# LS7366R_TestPRoject.net
KiCad netlist of a schematic drawn in EAGLE
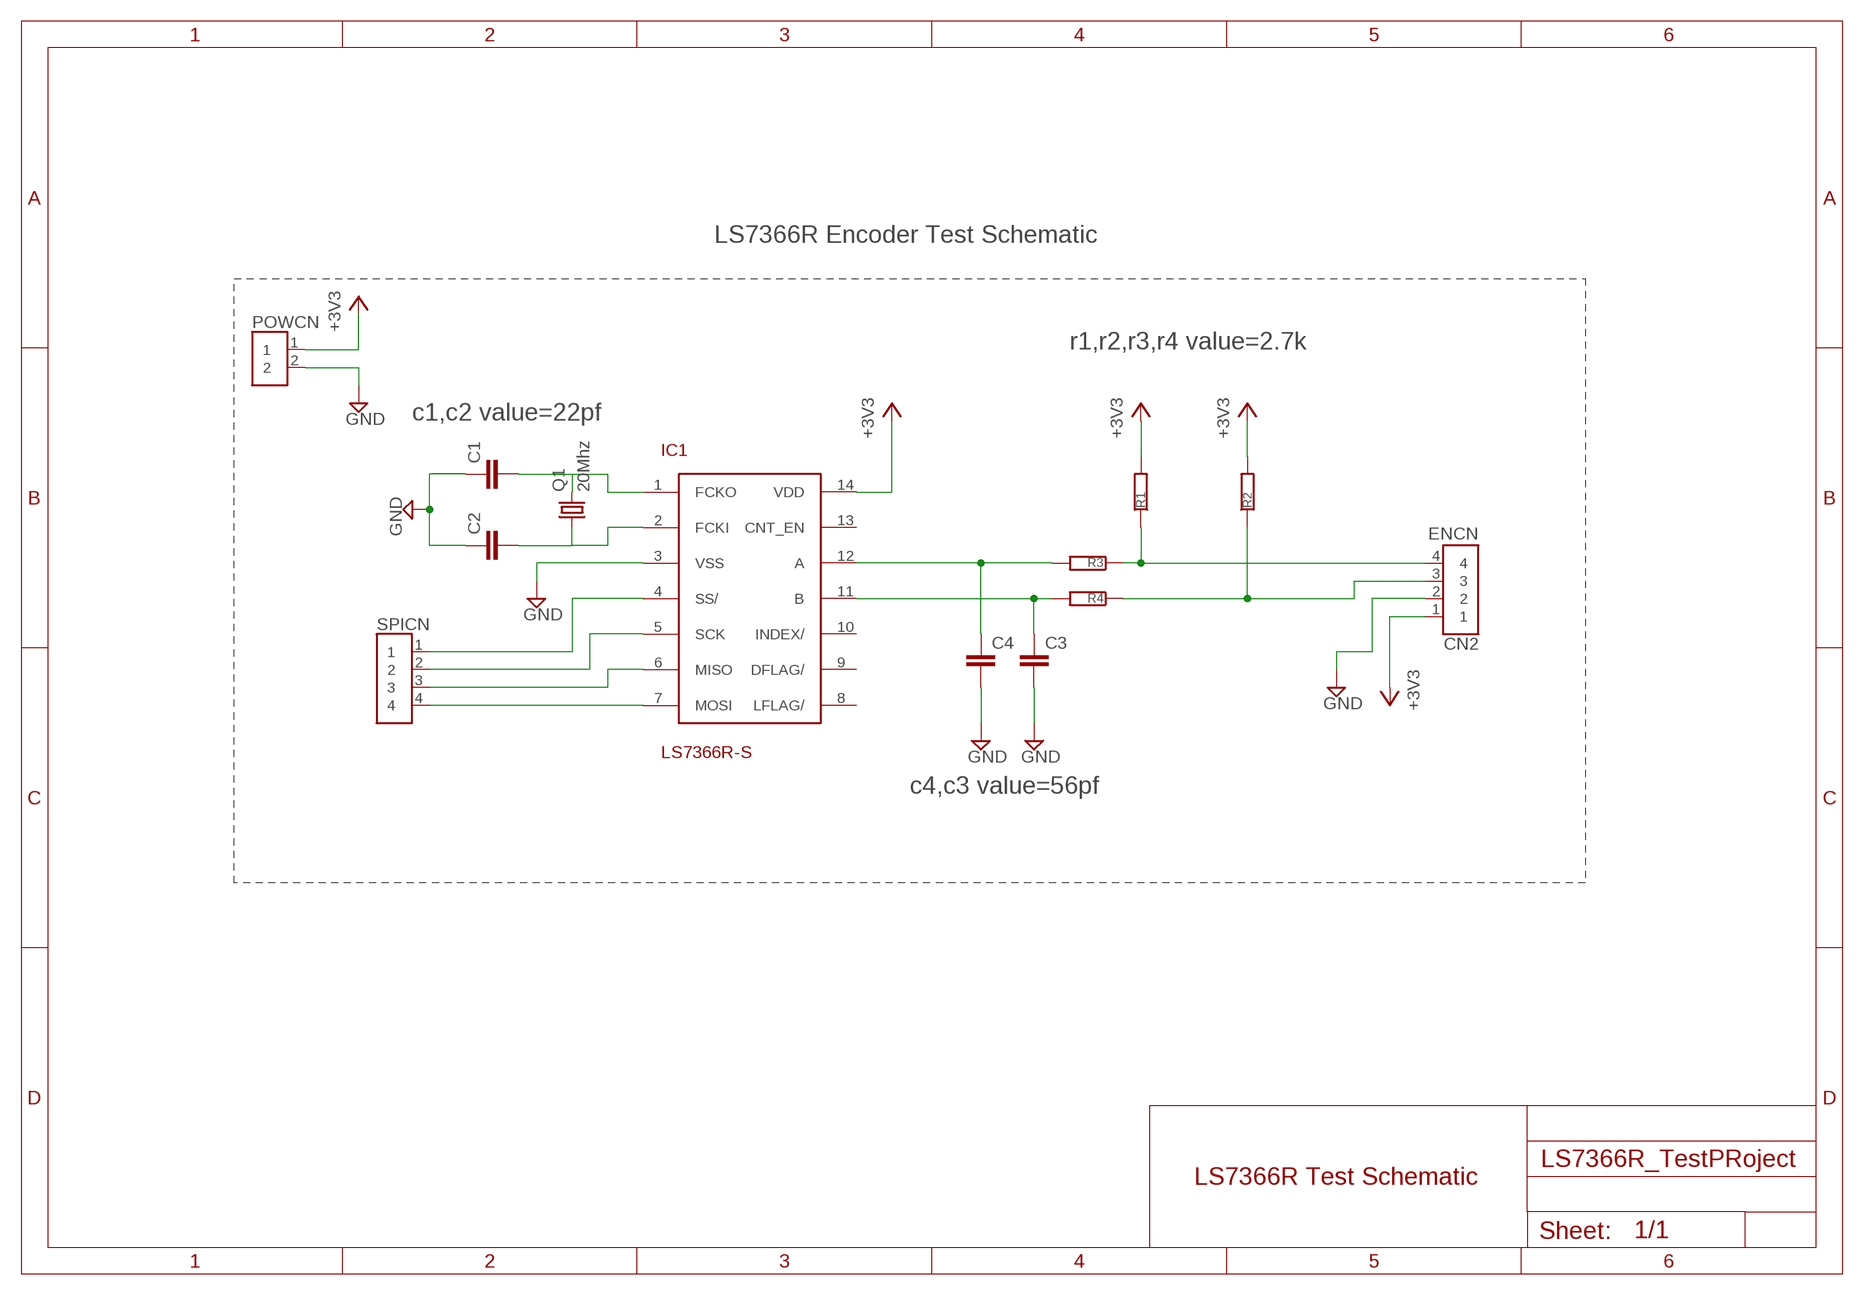
[diagram p0: schematic, sheet 1]

(export (version "E")
  (design (tool "Eeschema 10.0.6"))
  (components
    (comp (ref "C1")
      (value "22pf")
      (footprint "eagle-import:L0_0603")
      (libsource (lib "eagle-import") (part "CHIP_CAPACITOR_0603"))
    )
    (comp (ref "C2")
      (value "22pf")
      (footprint "eagle-import:L0_0603")
      (libsource (lib "eagle-import") (part "CHIP_CAPACITOR_0603"))
    )
    (comp (ref "C3")
      (value "56pf")
      (footprint "eagle-import:L0_0603")
      (libsource (lib "eagle-import") (part "CHIP_CAPACITOR_0603"))
    )
    (comp (ref "C4")
      (value "56pf")
      (footprint "eagle-import:L0_0603")
      (libsource (lib "eagle-import") (part "CHIP_CAPACITOR_0603"))
    )
    (comp (ref "CN2")
      (value "ENCN")
      (footprint "eagle-import:L0_TUNIK-4")
      (libsource (lib "eagle-import") (part "TUNIK-4PIN"))
    )
    (comp (ref "IC1")
      (value "LS7366R-S")
      (footprint "eagle-import:SOIC-14")
      (libsource (lib "eagle-import") (part "LS7366R-S"))
    )
    (comp (ref "POWCN")
      (value "TUNIK-2PIN")
      (footprint "eagle-import:L0_TUNIK-2")
      (libsource (lib "eagle-import") (part "TUNIK-2PIN"))
    )
    (comp (ref "Q1")
      (value "20Mhz")
      (footprint "eagle-import:L0_ABM3")
      (libsource (lib "eagle-import") (part "CRYSTAL_ABM3"))
    )
    (comp (ref "R1")
      (value "2.7k")
      (footprint "eagle-import:L0_0603")
      (libsource (lib "eagle-import") (part "CHIP_RESISTOR_0603"))
    )
    (comp (ref "R2")
      (value "2.7k")
      (footprint "eagle-import:L0_0603")
      (libsource (lib "eagle-import") (part "CHIP_RESISTOR_0603"))
    )
    (comp (ref "R3")
      (value "2.7k")
      (footprint "eagle-import:L0_0603")
      (libsource (lib "eagle-import") (part "CHIP_RESISTOR_0603"))
    )
    (comp (ref "R4")
      (value "2.7k")
      (footprint "eagle-import:L0_0603")
      (libsource (lib "eagle-import") (part "CHIP_RESISTOR_0603"))
    )
    (comp (ref "SPICN")
      (value "TUNIK-4PIN")
      (footprint "eagle-import:L0_TUNIK-4")
      (libsource (lib "eagle-import") (part "TUNIK-4PIN"))
    )
  )
  (nets
    (net (code "1") (name "+3V3") (class "Default")
      (node (ref "CN2") (pin "1") (pinfunction "1_1") (pintype "bidirectional"))
      (node (ref "IC1") (pin "14") (pinfunction "VDD_14") (pintype "bidirectional"))
      (node (ref "POWCN") (pin "1") (pinfunction "1_1") (pintype "bidirectional"))
      (node (ref "R1") (pin "2") (pinfunction "2_2") (pintype "passive"))
      (node (ref "R2") (pin "2") (pinfunction "2_2") (pintype "passive"))
    )
    (net (code "2") (name "GND") (class "Default")
      (node (ref "C1") (pin "2") (pinfunction "2_2") (pintype "passive"))
      (node (ref "C2") (pin "2") (pinfunction "2_2") (pintype "passive"))
      (node (ref "C3") (pin "1") (pinfunction "1_1") (pintype "passive"))
      (node (ref "C4") (pin "1") (pinfunction "1_1") (pintype "passive"))
      (node (ref "CN2") (pin "2") (pinfunction "2_2") (pintype "bidirectional"))
      (node (ref "IC1") (pin "3") (pinfunction "VSS_3") (pintype "bidirectional"))
      (node (ref "POWCN") (pin "2") (pinfunction "2_2") (pintype "bidirectional"))
    )
    (net (code "3") (name "Net-(CN2-Pad3)") (class "Default")
      (node (ref "CN2") (pin "3") (pinfunction "3_3") (pintype "bidirectional"))
      (node (ref "R2") (pin "1") (pinfunction "1_1") (pintype "passive"))
      (node (ref "R4") (pin "1") (pinfunction "1_1") (pintype "passive"))
    )
    (net (code "4") (name "Net-(CN2-Pad4)") (class "Default")
      (node (ref "CN2") (pin "4") (pinfunction "4_4") (pintype "bidirectional"))
      (node (ref "R1") (pin "1") (pinfunction "1_1") (pintype "passive"))
      (node (ref "R3") (pin "1") (pinfunction "1_1") (pintype "passive"))
    )
    (net (code "5") (name "Net-(IC1-A)") (class "Default")
      (node (ref "C4") (pin "2") (pinfunction "2_2") (pintype "passive"))
      (node (ref "IC1") (pin "12") (pinfunction "A_12") (pintype "bidirectional"))
      (node (ref "R3") (pin "2") (pinfunction "2_2") (pintype "passive"))
    )
    (net (code "6") (name "Net-(IC1-B)") (class "Default")
      (node (ref "C3") (pin "2") (pinfunction "2_2") (pintype "passive"))
      (node (ref "IC1") (pin "11") (pinfunction "B_11") (pintype "bidirectional"))
      (node (ref "R4") (pin "2") (pinfunction "2_2") (pintype "passive"))
    )
    (net (code "7") (name "Net-(IC1-FCKI)") (class "Default")
      (node (ref "C2") (pin "1") (pinfunction "1_1") (pintype "passive"))
      (node (ref "IC1") (pin "2") (pinfunction "FCKI_2") (pintype "bidirectional"))
      (node (ref "Q1") (pin "1") (pinfunction "1_1") (pintype "passive"))
    )
    (net (code "8") (name "Net-(IC1-FCKO)") (class "Default")
      (node (ref "C1") (pin "1") (pinfunction "1_1") (pintype "passive"))
      (node (ref "IC1") (pin "1") (pinfunction "FCKO_1") (pintype "bidirectional"))
      (node (ref "Q1") (pin "2") (pinfunction "2_2") (pintype "passive"))
    )
    (net (code "9") (name "Net-(IC1-MISO)") (class "Default")
      (node (ref "IC1") (pin "6") (pinfunction "MISO_6") (pintype "bidirectional"))
      (node (ref "SPICN") (pin "3") (pinfunction "3_3") (pintype "bidirectional"))
    )
    (net (code "10") (name "Net-(IC1-MOSI)") (class "Default")
      (node (ref "IC1") (pin "7") (pinfunction "MOSI_7") (pintype "bidirectional"))
      (node (ref "SPICN") (pin "4") (pinfunction "4_4") (pintype "bidirectional"))
    )
    (net (code "11") (name "Net-(IC1-SCK)") (class "Default")
      (node (ref "IC1") (pin "5") (pinfunction "SCK_5") (pintype "bidirectional"))
      (node (ref "SPICN") (pin "2") (pinfunction "2_2") (pintype "bidirectional"))
    )
    (net (code "12") (name "Net-(IC1-SS{slash})") (class "Default")
      (node (ref "IC1") (pin "4") (pinfunction "SS/_4") (pintype "bidirectional"))
      (node (ref "SPICN") (pin "1") (pinfunction "1_1") (pintype "bidirectional"))
    )
    (net (code "13") (name "unconnected-(IC1-CNT_EN-Pad13)") (class "Default")
      (node (ref "IC1") (pin "13") (pinfunction "CNT_EN_13") (pintype "bidirectional"))
    )
    (net (code "14") (name "unconnected-(IC1-DFLAG{slash}-Pad9)") (class "Default")
      (node (ref "IC1") (pin "9") (pinfunction "DFLAG/_9") (pintype "bidirectional"))
    )
    (net (code "15") (name "unconnected-(IC1-INDEX{slash}-Pad10)") (class "Default")
      (node (ref "IC1") (pin "10") (pinfunction "INDEX/_10") (pintype "bidirectional"))
    )
    (net (code "16") (name "unconnected-(IC1-LFLAG{slash}-Pad8)") (class "Default")
      (node (ref "IC1") (pin "8") (pinfunction "LFLAG/_8") (pintype "bidirectional"))
    )
  )
)
